# solar_collector_controller_V1_21.net
KiCad netlist of a schematic drawn in EAGLE
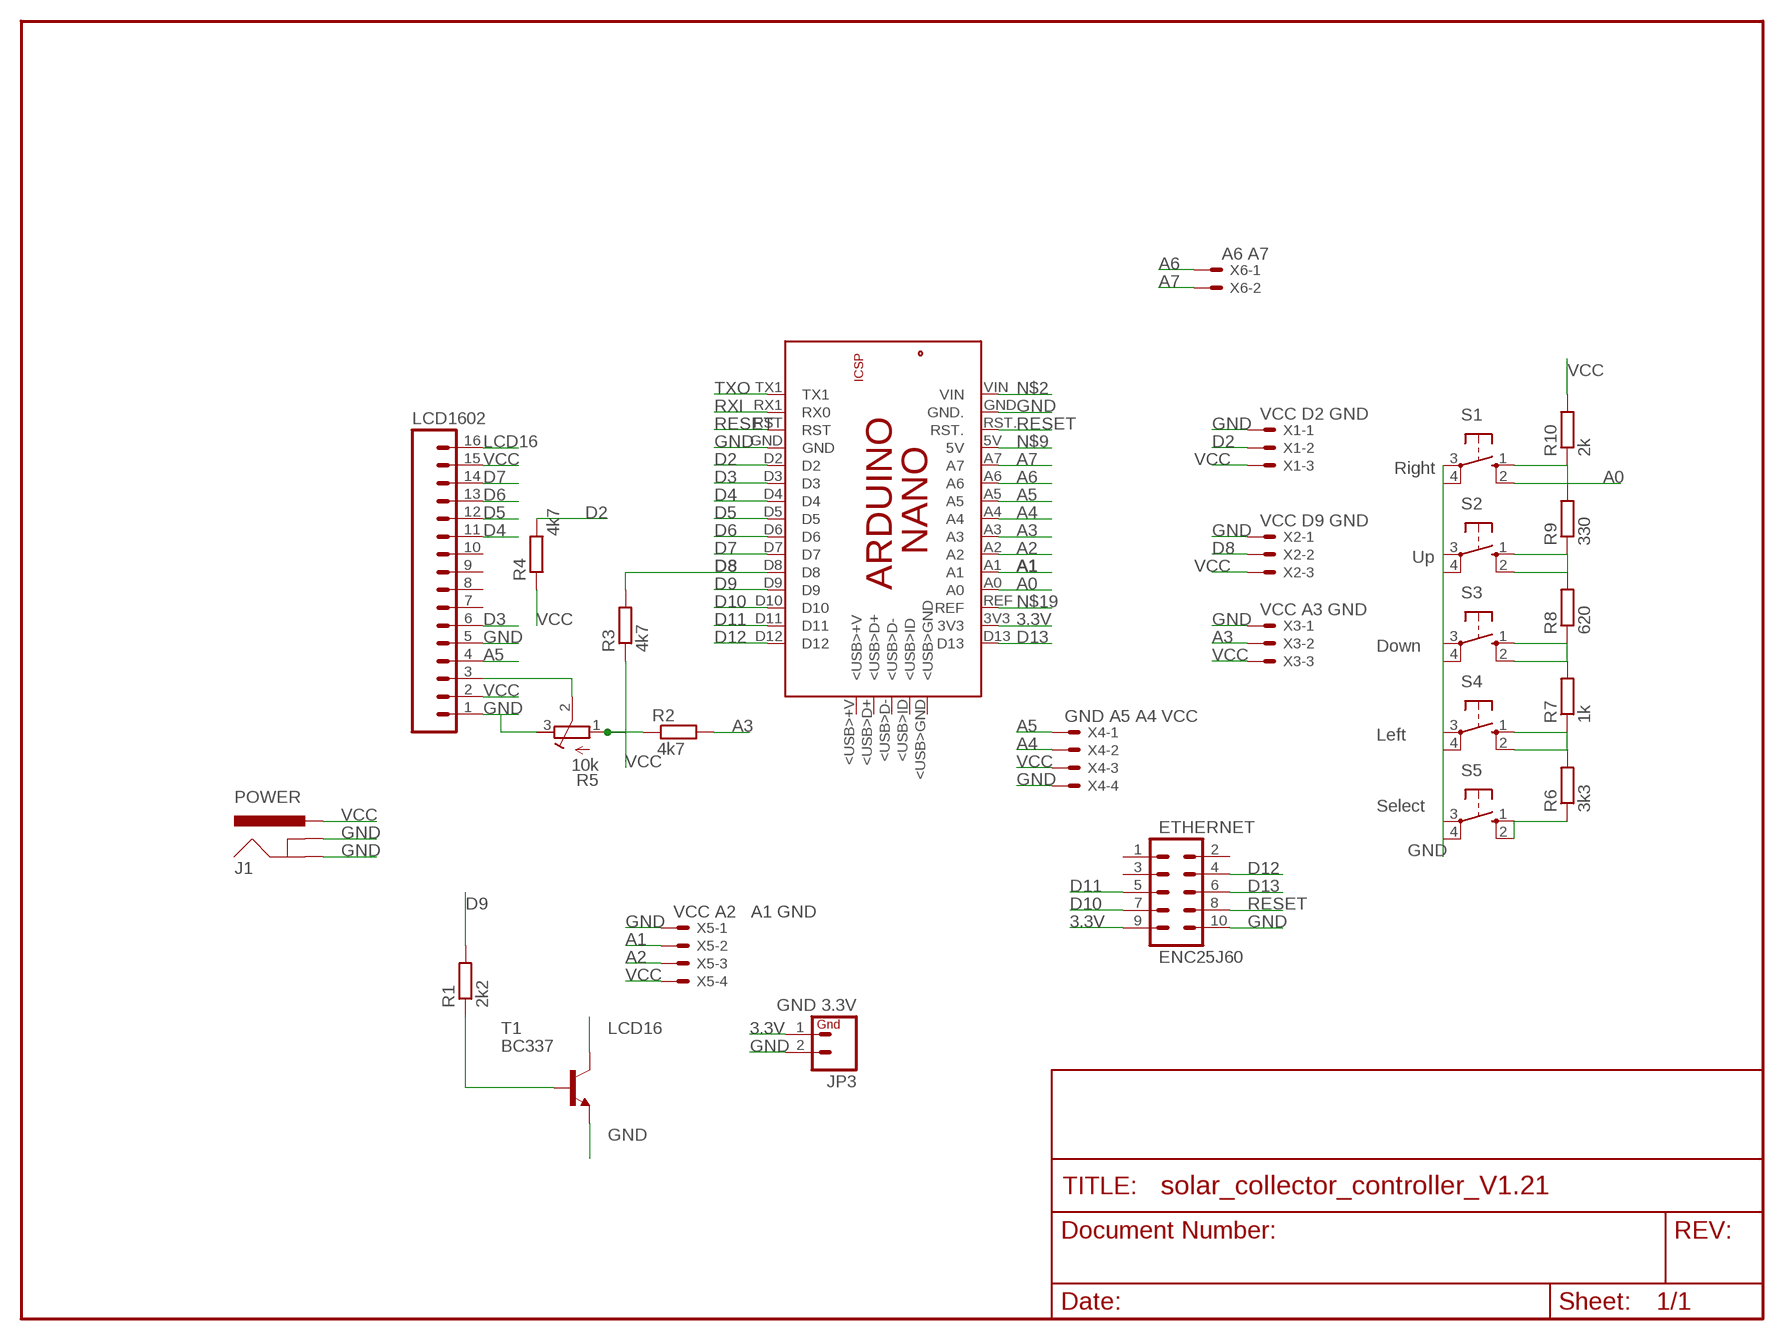
[diagram p0: schematic, sheet 1]

(export (version "E")
  (design (tool "Eeschema 10.0.6"))
  (components
    (comp (ref "ETHERNET")
      (value "ENC25J60")
      (footprint "eagle-import:AVR_ICSP")
      (libsource (lib "eagle-import") (part "M05X2PTH"))
    )
    (comp (ref "J1")
      (value "POWER")
      (footprint "eagle-import:POWER_JACK_PTH_LOCK")
      (libsource (lib "eagle-import") (part "POWER_JACKPTH_LOCK"))
    )
    (comp (ref "JP3")
      (value "GND 3.3V")
      (footprint "eagle-import:1X02")
      (libsource (lib "eagle-import") (part "M02PTH"))
    )
    (comp (ref "LCD1602")
      (value "HEADER-16P-2.54")
      (footprint "eagle-import:16P-2.54")
      (libsource (lib "eagle-import") (part "HEADER-16P-2.54"))
    )
    (comp (ref "PCB1")
      (value "ARDUINO_NANO")
      (footprint "eagle-import:ARDUINO_NANO")
      (libsource (lib "eagle-import") (part "ARDUINO_NANO"))
    )
    (comp (ref "R1")
      (value "2k2")
      (footprint "eagle-import:0207_10")
      (libsource (lib "eagle-import") (part "R-EU_0207/10"))
    )
    (comp (ref "R2")
      (value "4k7")
      (footprint "eagle-import:0207_10")
      (libsource (lib "eagle-import") (part "R-EU_0207/10"))
    )
    (comp (ref "R3")
      (value "4k7")
      (footprint "eagle-import:0207_10")
      (libsource (lib "eagle-import") (part "R-EU_0207/10"))
    )
    (comp (ref "R4")
      (value "4k7")
      (footprint "eagle-import:0207_10")
      (libsource (lib "eagle-import") (part "R-EU_0207/10"))
    )
    (comp (ref "R5")
      (value "10k")
      (footprint "eagle-import:RTRIM64W")
      (libsource (lib "eagle-import") (part "R-TRIMM64W"))
    )
    (comp (ref "R6")
      (value "3k3")
      (footprint "eagle-import:0207_10")
      (libsource (lib "eagle-import") (part "R-EU_0207/10"))
    )
    (comp (ref "R7")
      (value "1k")
      (footprint "eagle-import:0207_10")
      (libsource (lib "eagle-import") (part "R-EU_0207/10"))
    )
    (comp (ref "R8")
      (value "620")
      (footprint "eagle-import:0207_10")
      (libsource (lib "eagle-import") (part "R-EU_0207/10"))
    )
    (comp (ref "R9")
      (value "330")
      (footprint "eagle-import:0207_10")
      (libsource (lib "eagle-import") (part "R-EU_0207/10"))
    )
    (comp (ref "R10")
      (value "2k")
      (footprint "eagle-import:0207_10")
      (libsource (lib "eagle-import") (part "R-EU_0207/10"))
    )
    (comp (ref "S1")
      (value "Right")
      (footprint "eagle-import:B3F-10XX")
      (fields (field (name "MPN") "B3F-1000"))
      (libsource (lib "eagle-import") (part "10-XX"))
    )
    (comp (ref "S2")
      (value "Up")
      (footprint "eagle-import:B3F-10XX")
      (fields (field (name "MPN") "B3F-1000"))
      (libsource (lib "eagle-import") (part "10-XX"))
    )
    (comp (ref "S3")
      (value "Down")
      (footprint "eagle-import:B3F-10XX")
      (fields (field (name "MPN") "B3F-1000"))
      (libsource (lib "eagle-import") (part "10-XX"))
    )
    (comp (ref "S4")
      (value "Left")
      (footprint "eagle-import:B3F-10XX")
      (fields (field (name "MPN") "B3F-1000"))
      (libsource (lib "eagle-import") (part "10-XX"))
    )
    (comp (ref "S5")
      (value "Select")
      (footprint "eagle-import:B3F-10XX")
      (fields (field (name "MPN") "B3F-1000"))
      (libsource (lib "eagle-import") (part "10-XX"))
    )
    (comp (ref "T1")
      (value "BC337")
      (footprint "eagle-import:TO92")
      (libsource (lib "eagle-import") (part "BC337"))
    )
    (comp (ref "X1")
      (value "VCC D2 GND")
      (footprint "eagle-import:22-23-2031")
      (fields (field (name "MF") "MOLEX") (field (name "MPN") "22-23-2031"))
      (libsource (lib "eagle-import") (part "22-23-2031"))
    )
    (comp (ref "X2")
      (value "VCC D9 GND")
      (footprint "eagle-import:22-23-2031")
      (fields (field (name "MF") "MOLEX") (field (name "MPN") "22-23-2031"))
      (libsource (lib "eagle-import") (part "22-23-2031"))
    )
    (comp (ref "X3")
      (value "VCC A3 GND")
      (footprint "eagle-import:22-23-2031")
      (fields (field (name "MF") "MOLEX") (field (name "MPN") "22-23-2031"))
      (libsource (lib "eagle-import") (part "22-23-2031"))
    )
    (comp (ref "X4")
      (value "GND A5 A4 VCC")
      (footprint "eagle-import:22-23-2041")
      (fields (field (name "MF") "MOLEX") (field (name "MPN") "22-23-2041"))
      (libsource (lib "eagle-import") (part "22-23-2041"))
    )
    (comp (ref "X5")
      (value "VCC A2 A1 GND")
      (footprint "eagle-import:22-23-2041")
      (fields (field (name "MF") "MOLEX") (field (name "MPN") "22-23-2041"))
      (libsource (lib "eagle-import") (part "22-23-2041"))
    )
    (comp (ref "X6")
      (value "A6 A7")
      (footprint "eagle-import:22-23-2021")
      (fields (field (name "MF") "MOLEX") (field (name "MPN") "22-23-2021"))
      (libsource (lib "eagle-import") (part "22-23-2021"))
    )
  )
  (nets
    (net (code "1") (name "/3.3V") (class "Default")
      (node (ref "ETHERNET") (pin "9") (pinfunction "9_9") (pintype "passive"))
      (node (ref "JP3") (pin "1") (pinfunction "1_1") (pintype "passive"))
      (node (ref "PCB1") (pin "3V3") (pinfunction "3V3_3V3") (pintype "bidirectional"))
    )
    (net (code "2") (name "/A0") (class "Default")
      (node (ref "PCB1") (pin "A0") (pinfunction "A0_A0") (pintype "bidirectional"))
      (node (ref "R10") (pin "1") (pinfunction "1_1") (pintype "passive"))
      (node (ref "R9") (pin "2") (pinfunction "2_2") (pintype "passive"))
      (node (ref "S1") (pin "1") (pinfunction "S_1") (pintype "passive"))
      (node (ref "S1") (pin "2") (pinfunction "S1_2") (pintype "passive"))
    )
    (net (code "3") (name "/A1") (class "Default")
      (node (ref "PCB1") (pin "A1") (pinfunction "A1_A1") (pintype "bidirectional"))
      (node (ref "X5") (pin "2") (pinfunction "S_2") (pintype "passive"))
    )
    (net (code "4") (name "/A2") (class "Default")
      (node (ref "PCB1") (pin "A2") (pinfunction "A2_A2") (pintype "bidirectional"))
      (node (ref "X5") (pin "3") (pinfunction "S_3") (pintype "passive"))
    )
    (net (code "5") (name "/A3") (class "Default")
      (node (ref "PCB1") (pin "A3") (pinfunction "A3_A3") (pintype "bidirectional"))
      (node (ref "R2") (pin "2") (pinfunction "2_2") (pintype "passive"))
      (node (ref "X3") (pin "2") (pinfunction "S_2") (pintype "passive"))
    )
    (net (code "6") (name "/A4") (class "Default")
      (node (ref "PCB1") (pin "A4") (pinfunction "A4_A4") (pintype "bidirectional"))
      (node (ref "X4") (pin "2") (pinfunction "S_2") (pintype "passive"))
    )
    (net (code "7") (name "/A5") (class "Default")
      (node (ref "LCD1602") (pin "4") (pinfunction "4_4") (pintype "passive"))
      (node (ref "PCB1") (pin "A5") (pinfunction "A5_A5") (pintype "bidirectional"))
      (node (ref "X4") (pin "1") (pinfunction "S_1") (pintype "passive"))
    )
    (net (code "8") (name "/A6") (class "Default")
      (node (ref "PCB1") (pin "A6") (pinfunction "A6_A6") (pintype "bidirectional"))
      (node (ref "X6") (pin "1") (pinfunction "S_1") (pintype "passive"))
    )
    (net (code "9") (name "/A7") (class "Default")
      (node (ref "PCB1") (pin "A7") (pinfunction "A7_A7") (pintype "bidirectional"))
      (node (ref "X6") (pin "2") (pinfunction "S_2") (pintype "passive"))
    )
    (net (code "10") (name "/D2") (class "Default")
      (node (ref "PCB1") (pin "D2") (pinfunction "D2_D2") (pintype "bidirectional"))
      (node (ref "R4") (pin "2") (pinfunction "2_2") (pintype "passive"))
      (node (ref "X1") (pin "2") (pinfunction "S_2") (pintype "passive"))
    )
    (net (code "11") (name "/D3") (class "Default")
      (node (ref "LCD1602") (pin "6") (pinfunction "6_6") (pintype "passive"))
      (node (ref "PCB1") (pin "D3") (pinfunction "D3_D3") (pintype "bidirectional"))
    )
    (net (code "12") (name "/D4") (class "Default")
      (node (ref "LCD1602") (pin "11") (pinfunction "11_11") (pintype "passive"))
      (node (ref "PCB1") (pin "D4") (pinfunction "D4_D4") (pintype "bidirectional"))
    )
    (net (code "13") (name "/D5") (class "Default")
      (node (ref "LCD1602") (pin "12") (pinfunction "12_12") (pintype "passive"))
      (node (ref "PCB1") (pin "D5") (pinfunction "D5_D5") (pintype "bidirectional"))
    )
    (net (code "14") (name "/D6") (class "Default")
      (node (ref "LCD1602") (pin "13") (pinfunction "13_13") (pintype "passive"))
      (node (ref "PCB1") (pin "D6") (pinfunction "D6_D6") (pintype "bidirectional"))
    )
    (net (code "15") (name "/D7") (class "Default")
      (node (ref "LCD1602") (pin "14") (pinfunction "14_14") (pintype "passive"))
      (node (ref "PCB1") (pin "D7") (pinfunction "D7_D7") (pintype "bidirectional"))
    )
    (net (code "16") (name "/D8") (class "Default")
      (node (ref "PCB1") (pin "D8") (pinfunction "D8_D8") (pintype "bidirectional"))
      (node (ref "R3") (pin "2") (pinfunction "2_2") (pintype "passive"))
      (node (ref "X2") (pin "2") (pinfunction "S_2") (pintype "passive"))
    )
    (net (code "17") (name "/D9") (class "Default")
      (node (ref "PCB1") (pin "D9") (pinfunction "D9_D9") (pintype "bidirectional"))
      (node (ref "R1") (pin "2") (pinfunction "2_2") (pintype "passive"))
    )
    (net (code "18") (name "/D10") (class "Default")
      (node (ref "ETHERNET") (pin "7") (pinfunction "7_7") (pintype "passive"))
      (node (ref "PCB1") (pin "D10") (pinfunction "D10_D10") (pintype "bidirectional"))
    )
    (net (code "19") (name "/D11") (class "Default")
      (node (ref "ETHERNET") (pin "5") (pinfunction "5_5") (pintype "passive"))
      (node (ref "PCB1") (pin "D11") (pinfunction "D11_D11") (pintype "bidirectional"))
    )
    (net (code "20") (name "/D12") (class "Default")
      (node (ref "ETHERNET") (pin "4") (pinfunction "4_4") (pintype "passive"))
      (node (ref "PCB1") (pin "D12") (pinfunction "D12_D12") (pintype "bidirectional"))
    )
    (net (code "21") (name "/D13") (class "Default")
      (node (ref "ETHERNET") (pin "6") (pinfunction "6_6") (pintype "passive"))
      (node (ref "PCB1") (pin "D13") (pinfunction "D13_D13") (pintype "bidirectional"))
    )
    (net (code "22") (name "/GND") (class "Default")
      (node (ref "ETHERNET") (pin "10") (pinfunction "10_10") (pintype "passive"))
      (node (ref "J1") (pin "GND") (pinfunction "GND_GND") (pintype "bidirectional"))
      (node (ref "J1") (pin "GNDBREAK") (pinfunction "GNDBREAK_GNDBREAK") (pintype "bidirectional"))
      (node (ref "JP3") (pin "2") (pinfunction "2_2") (pintype "passive"))
      (node (ref "LCD1602") (pin "1") (pinfunction "1_1") (pintype "passive"))
      (node (ref "LCD1602") (pin "5") (pinfunction "5_5") (pintype "passive"))
      (node (ref "PCB1") (pin "GND") (pinfunction "GND_GND") (pintype "bidirectional"))
      (node (ref "PCB1") (pin "GND.") (pinfunction "GND._GND.") (pintype "bidirectional"))
      (node (ref "R5") (pin "3") (pinfunction "A_3") (pintype "passive"))
      (node (ref "S1") (pin "3") (pinfunction "P_3") (pintype "passive"))
      (node (ref "S1") (pin "4") (pinfunction "P1_4") (pintype "passive"))
      (node (ref "S2") (pin "3") (pinfunction "P_3") (pintype "passive"))
      (node (ref "S2") (pin "4") (pinfunction "P1_4") (pintype "passive"))
      (node (ref "S3") (pin "3") (pinfunction "P_3") (pintype "passive"))
      (node (ref "S3") (pin "4") (pinfunction "P1_4") (pintype "passive"))
      (node (ref "S4") (pin "3") (pinfunction "P_3") (pintype "passive"))
      (node (ref "S4") (pin "4") (pinfunction "P1_4") (pintype "passive"))
      (node (ref "S5") (pin "3") (pinfunction "P_3") (pintype "passive"))
      (node (ref "S5") (pin "4") (pinfunction "P1_4") (pintype "passive"))
      (node (ref "T1") (pin "1") (pinfunction "E_1") (pintype "passive"))
      (node (ref "X1") (pin "1") (pinfunction "S_1") (pintype "passive"))
      (node (ref "X2") (pin "1") (pinfunction "S_1") (pintype "passive"))
      (node (ref "X3") (pin "1") (pinfunction "S_1") (pintype "passive"))
      (node (ref "X4") (pin "4") (pinfunction "S_4") (pintype "passive"))
      (node (ref "X5") (pin "1") (pinfunction "S_1") (pintype "passive"))
    )
    (net (code "23") (name "/LCD16") (class "Default")
      (node (ref "LCD1602") (pin "16") (pinfunction "16_16") (pintype "passive"))
      (node (ref "T1") (pin "3") (pinfunction "C_3") (pintype "passive"))
    )
    (net (code "24") (name "/N$2") (class "Default")
      (node (ref "PCB1") (pin "VIN") (pinfunction "VIN_VIN") (pintype "bidirectional"))
    )
    (net (code "25") (name "/N$9") (class "Default")
      (node (ref "PCB1") (pin "5V") (pinfunction "5V_5V") (pintype "bidirectional"))
    )
    (net (code "26") (name "/N$19") (class "Default")
      (node (ref "PCB1") (pin "REF") (pinfunction "REF_REF") (pintype "bidirectional"))
    )
    (net (code "27") (name "/RESET") (class "Default")
      (node (ref "ETHERNET") (pin "8") (pinfunction "8_8") (pintype "passive"))
      (node (ref "PCB1") (pin "RST") (pinfunction "RST_RST") (pintype "bidirectional"))
      (node (ref "PCB1") (pin "RST.") (pinfunction "RST._RST.") (pintype "bidirectional"))
    )
    (net (code "28") (name "/RXI") (class "Default")
      (node (ref "PCB1") (pin "RX1") (pinfunction "RX0_RX1") (pintype "bidirectional"))
    )
    (net (code "29") (name "/TXO") (class "Default")
      (node (ref "PCB1") (pin "TX1") (pinfunction "TX1_TX1") (pintype "bidirectional"))
    )
    (net (code "30") (name "/VCC") (class "Default")
      (node (ref "J1") (pin "PWR") (pinfunction "PWR_PWR") (pintype "bidirectional"))
      (node (ref "LCD1602") (pin "15") (pinfunction "15_15") (pintype "passive"))
      (node (ref "LCD1602") (pin "2") (pinfunction "2_2") (pintype "passive"))
      (node (ref "R10") (pin "2") (pinfunction "2_2") (pintype "passive"))
      (node (ref "R2") (pin "1") (pinfunction "1_1") (pintype "passive"))
      (node (ref "R3") (pin "1") (pinfunction "1_1") (pintype "passive"))
      (node (ref "R4") (pin "1") (pinfunction "1_1") (pintype "passive"))
      (node (ref "R5") (pin "1") (pinfunction "E_1") (pintype "passive"))
      (node (ref "X1") (pin "3") (pinfunction "S_3") (pintype "passive"))
      (node (ref "X2") (pin "3") (pinfunction "S_3") (pintype "passive"))
      (node (ref "X3") (pin "3") (pinfunction "S_3") (pintype "passive"))
      (node (ref "X4") (pin "3") (pinfunction "S_3") (pintype "passive"))
      (node (ref "X5") (pin "4") (pinfunction "S_4") (pintype "passive"))
    )
    (net (code "31") (name "Net-(R5-S)") (class "Default")
      (node (ref "LCD1602") (pin "3") (pinfunction "3_3") (pintype "passive"))
      (node (ref "R5") (pin "2") (pinfunction "S_2") (pintype "passive"))
    )
    (net (code "32") (name "Net-(S2-S)") (class "Default")
      (node (ref "R8") (pin "2") (pinfunction "2_2") (pintype "passive"))
      (node (ref "R9") (pin "1") (pinfunction "1_1") (pintype "passive"))
      (node (ref "S2") (pin "1") (pinfunction "S_1") (pintype "passive"))
      (node (ref "S2") (pin "2") (pinfunction "S1_2") (pintype "passive"))
    )
    (net (code "33") (name "Net-(S3-S)") (class "Default")
      (node (ref "R7") (pin "2") (pinfunction "2_2") (pintype "passive"))
      (node (ref "R8") (pin "1") (pinfunction "1_1") (pintype "passive"))
      (node (ref "S3") (pin "1") (pinfunction "S_1") (pintype "passive"))
      (node (ref "S3") (pin "2") (pinfunction "S1_2") (pintype "passive"))
    )
    (net (code "34") (name "Net-(S4-S)") (class "Default")
      (node (ref "R6") (pin "2") (pinfunction "2_2") (pintype "passive"))
      (node (ref "R7") (pin "1") (pinfunction "1_1") (pintype "passive"))
      (node (ref "S4") (pin "1") (pinfunction "S_1") (pintype "passive"))
      (node (ref "S4") (pin "2") (pinfunction "S1_2") (pintype "passive"))
    )
    (net (code "35") (name "Net-(S5-S)") (class "Default")
      (node (ref "R6") (pin "1") (pinfunction "1_1") (pintype "passive"))
      (node (ref "S5") (pin "1") (pinfunction "S_1") (pintype "passive"))
      (node (ref "S5") (pin "2") (pinfunction "S1_2") (pintype "passive"))
    )
    (net (code "36") (name "Net-(T1-B)") (class "Default")
      (node (ref "R1") (pin "1") (pinfunction "1_1") (pintype "passive"))
      (node (ref "T1") (pin "2") (pinfunction "B_2") (pintype "passive"))
    )
    (net (code "37") (name "unconnected-(ETHERNET-Pad1)") (class "Default")
      (node (ref "ETHERNET") (pin "1") (pinfunction "1_1") (pintype "passive"))
    )
    (net (code "38") (name "unconnected-(ETHERNET-Pad2)") (class "Default")
      (node (ref "ETHERNET") (pin "2") (pinfunction "2_2") (pintype "passive"))
    )
    (net (code "39") (name "unconnected-(ETHERNET-Pad3)") (class "Default")
      (node (ref "ETHERNET") (pin "3") (pinfunction "3_3") (pintype "passive"))
    )
    (net (code "40") (name "unconnected-(LCD1602-Pad7)") (class "Default")
      (node (ref "LCD1602") (pin "7") (pinfunction "7_7") (pintype "passive"))
    )
    (net (code "41") (name "unconnected-(LCD1602-Pad8)") (class "Default")
      (node (ref "LCD1602") (pin "8") (pinfunction "8_8") (pintype "passive"))
    )
    (net (code "42") (name "unconnected-(LCD1602-Pad9)") (class "Default")
      (node (ref "LCD1602") (pin "9") (pinfunction "9_9") (pintype "passive"))
    )
    (net (code "43") (name "unconnected-(LCD1602-Pad10)") (class "Default")
      (node (ref "LCD1602") (pin "10") (pinfunction "10_10") (pintype "passive"))
    )
    (net (code "44") (name "unconnected-(PCB1-Pad5V.)") (class "Default")
      (node (ref "PCB1") (pin "5V.") (pinfunction "5V._5V.") (pintype "bidirectional"))
    )
    (net (code "45") (name "unconnected-(PCB1-Pad<USB>+V)") (class "Default")
      (node (ref "PCB1") (pin "<USB>+V") (pinfunction "<USB>+V_<USB>+V") (pintype "bidirectional"))
    )
    (net (code "46") (name "unconnected-(PCB1-Pad<USB>D+)") (class "Default")
      (node (ref "PCB1") (pin "<USB>D+") (pinfunction "<USB>D+_<USB>D+") (pintype "bidirectional"))
    )
    (net (code "47") (name "unconnected-(PCB1-Pad<USB>D-)") (class "Default")
      (node (ref "PCB1") (pin "<USB>D-") (pinfunction "<USB>D-_<USB>D-") (pintype "bidirectional"))
    )
    (net (code "48") (name "unconnected-(PCB1-Pad<USB>GND)") (class "Default")
      (node (ref "PCB1") (pin "<USB>GND") (pinfunction "<USB>GND_<USB>GND") (pintype "bidirectional"))
    )
    (net (code "49") (name "unconnected-(PCB1-Pad<USB>ID)") (class "Default")
      (node (ref "PCB1") (pin "<USB>ID") (pinfunction "<USB>ID_<USB>ID") (pintype "bidirectional"))
    )
    (net (code "50") (name "unconnected-(PCB1-PadGND_)") (class "Default")
      (node (ref "PCB1") (pin "GND_") (pinfunction "GND__GND_") (pintype "bidirectional"))
    )
    (net (code "51") (name "unconnected-(PCB1-PadMISO)") (class "Default")
      (node (ref "PCB1") (pin "MISO") (pinfunction "MISO_MISO") (pintype "bidirectional"))
    )
    (net (code "52") (name "unconnected-(PCB1-PadMOSI)") (class "Default")
      (node (ref "PCB1") (pin "MOSI") (pinfunction "MOSI_MOSI") (pintype "bidirectional"))
    )
    (net (code "53") (name "unconnected-(PCB1-PadRESET..)") (class "Default")
      (node (ref "PCB1") (pin "RESET..") (pinfunction "RESET.._RESET..") (pintype "bidirectional"))
    )
    (net (code "54") (name "unconnected-(PCB1-PadSCK)") (class "Default")
      (node (ref "PCB1") (pin "SCK") (pinfunction "SCK_SCK") (pintype "bidirectional"))
    )
  )
)
